# TTTQ20_STM32-project__Schematic1_4__1_P1.net
KiCad netlist of a schematic drawn in Altium Designer
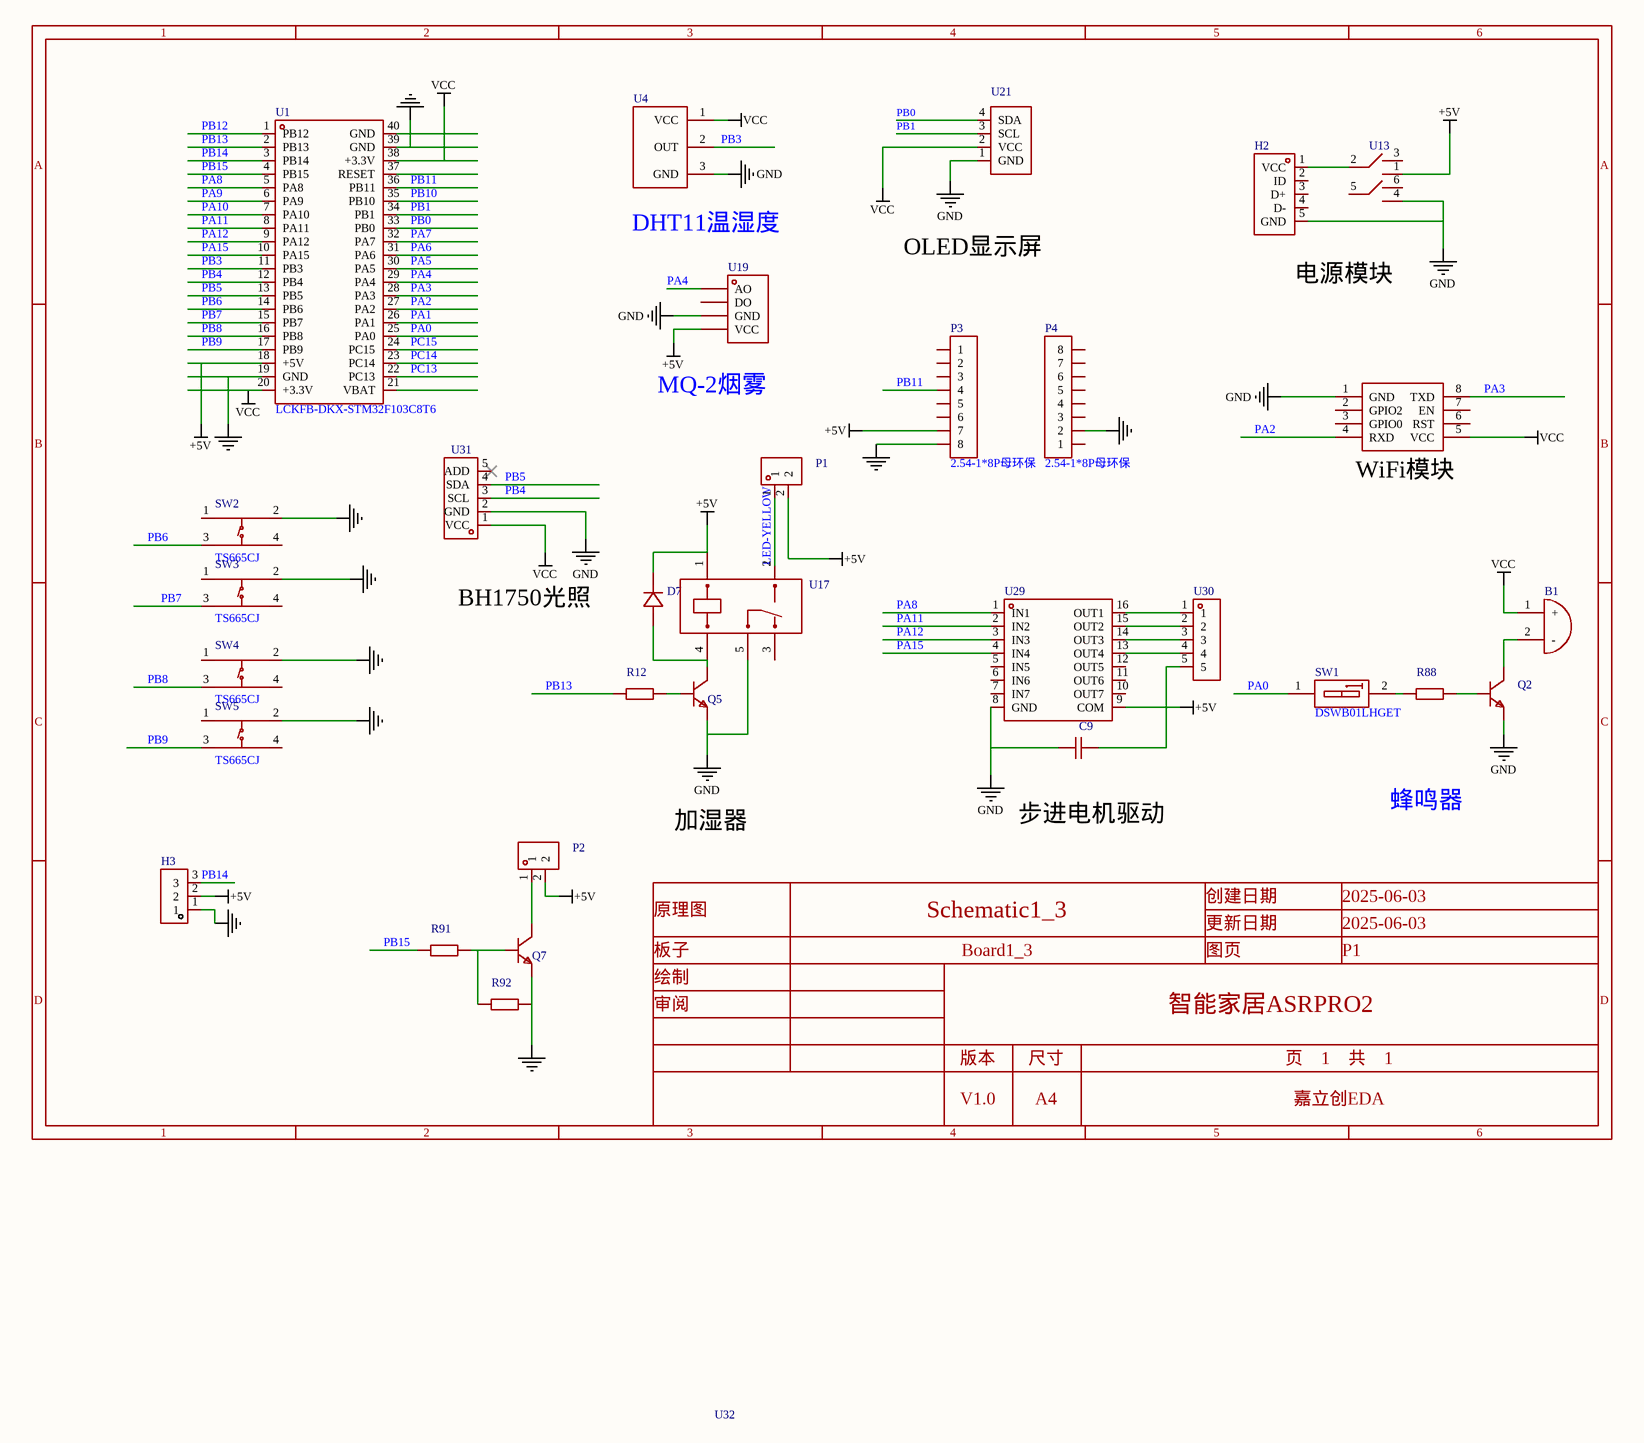
[diagram p0: TTTQ20_STM32-project__Schematic1_4__1_P1.schdoc]

(export (version "E")
  (design (tool "Eeschema 10.0.6"))
  (components
    (comp (ref "B1")
      (value "蜂鸣器FMQ")
      (footprint "footprint_3c01")
      (libsource (lib "altium-import") (part "root_0_蜂鸣器FMQ_"))
    )
    (comp (ref "C9")
      (value "瓷片电容47PF  3KV")
      (footprint "CAP-TH_L5.0-W4.0-P5.00-D1.0")
      (libsource (lib "altium-import") (part "root_0_瓷片电容47PF  3KV_"))
    )
    (comp (ref "D7")
      (value "D_1N4007A")
      (footprint "DO_1N4007")
      (libsource (lib "altium-import") (part "root_1_D_1N4007A_"))
    )
    (comp (ref "H2")
      (value "mini USB")
      (footprint "MINI-USB-POWER")
      (libsource (lib "altium-import") (part "root_0_mini USB_"))
    )
    (comp (ref "H3")
      (value "~")
      (footprint "HDR-TH_3P-P2.54-V-F")
      (libsource (lib "altium-import") (part "root_2_HDR-F_2.54_1x3P_"))
    )
    (comp (ref "P1")
      (value "XH2.54直插座-2P")
      (footprint "CONN-TH_XH2.54-2P")
      (libsource (lib "altium-import") (part "root_1_XH2.54直插座-2P_"))
    )
    (comp (ref "P2")
      (value "XH2.54直插座-2P")
      (footprint "CONN-TH_XH2.54-2P")
      (libsource (lib "altium-import") (part "root_1_XH2.54直插座-2P_"))
    )
    (comp (ref "P3")
      (value "2.54-1*8P母环保")
      (footprint "HDR-TH_8P-P2.54-V-F-1")
      (fields (field (name "MANUFACTURER") "BOOMELE(博穆精密)"))
      (libsource (lib "altium-import") (part "root_0_2.54-1*8P母环保_"))
    )
    (comp (ref "P4")
      (value "2.54-1*8P母环保")
      (footprint "HDR-TH_8P-P2.54-V-F-1")
      (fields (field (name "MANUFACTURER") "BOOMELE(博穆精密)"))
      (libsource (lib "altium-import") (part "root_2_2.54-1*8P母环保_"))
    )
    (comp (ref "Q2")
      (value "S8050_TO_NPN")
      (footprint "S8050_TO_92")
      (libsource (lib "altium-import") (part "root_0_S8050_TO_NPN_"))
    )
    (comp (ref "Q5")
      (value "S8050_TO_NPN")
      (footprint "S8050_TO_92")
      (libsource (lib "altium-import") (part "root_0_S8050_TO_NPN_"))
    )
    (comp (ref "Q7")
      (value "S8050_TO_NPN")
      (footprint "S8050_TO_92")
      (libsource (lib "altium-import") (part "root_0_S8050_TO_NPN_"))
    )
    (comp (ref "R12")
      (value "1K")
      (footprint "Res_1/4W")
      (libsource (lib "altium-import") (part "root_2_1K_"))
    )
    (comp (ref "R88")
      (value "10kΩ")
      (footprint "Res_1/4W")
      (libsource (lib "altium-import") (part "root_0_10kΩ_"))
    )
    (comp (ref "R91")
      (value "10kΩ")
      (footprint "Res_1/4W")
      (libsource (lib "altium-import") (part "root_0_10kΩ_"))
    )
    (comp (ref "R92")
      (value "10kΩ")
      (footprint "Res_1/4W")
      (libsource (lib "altium-import") (part "root_0_10kΩ_"))
    )
    (comp (ref "SW1")
      (value "DSWB01LHGET")
      (footprint "SW-TH_DSWB01LHGET")
      (fields (field (name "MANUFACTURER") "YE"))
      (libsource (lib "altium-import") (part "root_0_DSWB01LHGET_"))
    )
    (comp (ref "SW2")
      (value "TS665CJ")
      (footprint "SW-TH_4P-L6.0-W6.0-P4.50-LS6.5")
      (fields (field (name "MANUFACTURER") "SHOU HAN(首韩)"))
      (libsource (lib "altium-import") (part "root_0_TS665CJ_"))
    )
    (comp (ref "SW3")
      (value "TS665CJ")
      (footprint "SW-TH_4P-L6.0-W6.0-P4.50-LS6.5")
      (fields (field (name "MANUFACTURER") "SHOU HAN(首韩)"))
      (libsource (lib "altium-import") (part "root_0_TS665CJ_"))
    )
    (comp (ref "SW4")
      (value "TS665CJ")
      (footprint "SW-TH_4P-L6.0-W6.0-P4.50-LS6.5")
      (fields (field (name "MANUFACTURER") "SHOU HAN(首韩)"))
      (libsource (lib "altium-import") (part "root_0_TS665CJ_"))
    )
    (comp (ref "SW5")
      (value "TS665CJ")
      (footprint "SW-TH_4P-L6.0-W6.0-P4.50-LS6.5")
      (fields (field (name "MANUFACTURER") "SHOU HAN(首韩)"))
      (libsource (lib "altium-import") (part "root_0_TS665CJ_"))
    )
    (comp (ref "U1")
      (value "LCKFB-DKX-STM32F103C8T6")
      (footprint "CONN-TH_L53.3-W22.9_STM32F103C8T6-CARD")
      (fields (field (name "MANUFACTURER") "立创开发板"))
      (libsource (lib "altium-import") (part "root_0_LCKFB-DKX-STM32F103C8T6_"))
    )
    (comp (ref "U4")
      (value "DHT11温湿度传感器")
      (footprint "DHT11")
      (libsource (lib "altium-import") (part "root_2_DHT11温湿度传感器_"))
    )
    (comp (ref "U13")
      (value "按键开关7*7")
      (footprint "footprint_7245")
      (libsource (lib "altium-import") (part "root_0_按键开关7*7_"))
    )
    (comp (ref "U17")
      (value "继电器5V")
      (footprint "footprint_0775")
      (libsource (lib "altium-import") (part "root_3_继电器5V_"))
    )
    (comp (ref "U19")
      (value "MQ系列4针传感器")
      (footprint "footprint_df71")
      (libsource (lib "altium-import") (part "root_0_MQ系列4针传感器_"))
    )
    (comp (ref "U21")
      (value "OLED四针0.96寸")
      (footprint "footprint_0ab5")
      (libsource (lib "altium-import") (part "root_0_OLED四针0.96寸_"))
    )
    (comp (ref "U29")
      (value "ULN2003A")
      (footprint "DIP-16_L20.0-W6.4-P2.54-LS7.6-BL")
      (fields (field (name "MANUFACTURER") "ST(意法半导体)"))
      (libsource (lib "altium-import") (part "root_0_ULN2003A_"))
    )
    (comp (ref "U30")
      (value "步进电机")
      (footprint "conn-th_5p-p2.54_xh2.54_5p_dip")
      (libsource (lib "altium-import") (part "root_0_步进电机_"))
    )
    (comp (ref "U31")
      (value "GY302光照传感器")
      (footprint "footprint_6163")
      (libsource (lib "altium-import") (part "root_0_GY302光照传感器_"))
    )
    (comp (ref "U32")
      (value "ESP8266-01S模块")
      (footprint "footprint_fe65")
      (libsource (lib "altium-import") (part "root_0_ESP8266-01S模块_"))
    )
  )
  (nets
    (net (code "1") (name "+5V") (class "Default")
      (node (ref "C9") (pin "2") (pinfunction "2_2") (pintype "passive"))
      (node (ref "D7") (pin "1") (pinfunction "K_1") (pintype "passive"))
      (node (ref "H3") (pin "2") (pinfunction "2_2") (pintype "passive"))
      (node (ref "P1") (pin "2") (pinfunction "2_2") (pintype "passive"))
      (node (ref "P2") (pin "2") (pinfunction "2_2") (pintype "passive"))
      (node (ref "P3") (pin "7") (pinfunction "7_7") (pintype "passive"))
      (node (ref "U1") (pin "18") (pinfunction "+5V_18") (pintype "passive"))
      (node (ref "U13") (pin "1") (pinfunction "1_1") (pintype "passive"))
      (node (ref "U17") (pin "1") (pinfunction "1_1") (pintype "passive"))
      (node (ref "U19") (pin "4") (pinfunction "VCC_4") (pintype "passive"))
      (node (ref "U29") (pin "9") (pinfunction "COM_9") (pintype "passive"))
      (node (ref "U30") (pin "5") (pinfunction "5_5") (pintype "passive"))
    )
    (net (code "2") (name "/LED-YELLOW") (class "Default")
      (node (ref "P1") (pin "1") (pinfunction "1_1") (pintype "passive"))
      (node (ref "U17") (pin "2") (pinfunction "2_2") (pintype "passive"))
    )
    (net (code "3") (name "/PA0") (class "Default")
      (node (ref "SW1") (pin "1") (pinfunction "A1_1") (pintype "passive"))
      (node (ref "U1") (pin "25") (pinfunction "PA0_25") (pintype "passive"))
    )
    (net (code "4") (name "/PA1") (class "Default")
      (node (ref "U1") (pin "26") (pinfunction "PA1_26") (pintype "passive"))
    )
    (net (code "5") (name "/PA2") (class "Default")
      (node (ref "U1") (pin "27") (pinfunction "PA2_27") (pintype "passive"))
      (node (ref "U32") (pin "4") (pinfunction "RXD_4") (pintype "passive"))
    )
    (net (code "6") (name "/PA3") (class "Default")
      (node (ref "U1") (pin "28") (pinfunction "PA3_28") (pintype "passive"))
      (node (ref "U32") (pin "8") (pinfunction "TXD_8") (pintype "passive"))
    )
    (net (code "7") (name "/PA4") (class "Default")
      (node (ref "U1") (pin "29") (pinfunction "PA4_29") (pintype "passive"))
      (node (ref "U19") (pin "1") (pinfunction "AO_1") (pintype "passive"))
    )
    (net (code "8") (name "/PA5") (class "Default")
      (node (ref "U1") (pin "30") (pinfunction "PA5_30") (pintype "passive"))
    )
    (net (code "9") (name "/PA6") (class "Default")
      (node (ref "U1") (pin "31") (pinfunction "PA6_31") (pintype "passive"))
    )
    (net (code "10") (name "/PA7") (class "Default")
      (node (ref "U1") (pin "32") (pinfunction "PA7_32") (pintype "passive"))
    )
    (net (code "11") (name "/PA8") (class "Default")
      (node (ref "U1") (pin "5") (pinfunction "PA8_5") (pintype "passive"))
      (node (ref "U29") (pin "1") (pinfunction "IN1_1") (pintype "passive"))
    )
    (net (code "12") (name "/PA9") (class "Default")
      (node (ref "U1") (pin "6") (pinfunction "PA9_6") (pintype "passive"))
    )
    (net (code "13") (name "/PA10") (class "Default")
      (node (ref "U1") (pin "7") (pinfunction "PA10_7") (pintype "passive"))
    )
    (net (code "14") (name "/PA11") (class "Default")
      (node (ref "U1") (pin "8") (pinfunction "PA11_8") (pintype "passive"))
      (node (ref "U29") (pin "2") (pinfunction "IN2_2") (pintype "passive"))
    )
    (net (code "15") (name "/PA12") (class "Default")
      (node (ref "U1") (pin "9") (pinfunction "PA12_9") (pintype "passive"))
      (node (ref "U29") (pin "3") (pinfunction "IN3_3") (pintype "passive"))
    )
    (net (code "16") (name "/PA15") (class "Default")
      (node (ref "U1") (pin "10") (pinfunction "PA15_10") (pintype "passive"))
      (node (ref "U29") (pin "4") (pinfunction "IN4_4") (pintype "passive"))
    )
    (net (code "17") (name "/PB0") (class "Default")
      (node (ref "U1") (pin "33") (pinfunction "PB0_33") (pintype "passive"))
      (node (ref "U21") (pin "4") (pinfunction "SDA_4") (pintype "passive"))
    )
    (net (code "18") (name "/PB1") (class "Default")
      (node (ref "U1") (pin "34") (pinfunction "PB1_34") (pintype "passive"))
      (node (ref "U21") (pin "3") (pinfunction "SCL_3") (pintype "passive"))
    )
    (net (code "19") (name "/PB3") (class "Default")
      (node (ref "U1") (pin "11") (pinfunction "PB3_11") (pintype "passive"))
      (node (ref "U4") (pin "2") (pinfunction "OUT_2") (pintype "passive"))
    )
    (net (code "20") (name "/PB4") (class "Default")
      (node (ref "U1") (pin "12") (pinfunction "PB4_12") (pintype "passive"))
      (node (ref "U31") (pin "3") (pinfunction "SCL_3") (pintype "passive"))
    )
    (net (code "21") (name "/PB5") (class "Default")
      (node (ref "U1") (pin "13") (pinfunction "PB5_13") (pintype "passive"))
      (node (ref "U31") (pin "4") (pinfunction "SDA_4") (pintype "passive"))
    )
    (net (code "22") (name "/PB6") (class "Default")
      (node (ref "SW2") (pin "3") (pinfunction "C_3") (pintype "passive"))
      (node (ref "U1") (pin "14") (pinfunction "PB6_14") (pintype "passive"))
    )
    (net (code "23") (name "/PB7") (class "Default")
      (node (ref "SW3") (pin "3") (pinfunction "C_3") (pintype "passive"))
      (node (ref "U1") (pin "15") (pinfunction "PB7_15") (pintype "passive"))
    )
    (net (code "24") (name "/PB8") (class "Default")
      (node (ref "SW4") (pin "3") (pinfunction "C_3") (pintype "passive"))
      (node (ref "U1") (pin "16") (pinfunction "PB8_16") (pintype "passive"))
    )
    (net (code "25") (name "/PB9") (class "Default")
      (node (ref "SW5") (pin "3") (pinfunction "C_3") (pintype "passive"))
      (node (ref "U1") (pin "17") (pinfunction "PB9_17") (pintype "passive"))
    )
    (net (code "26") (name "/PB10") (class "Default")
      (node (ref "U1") (pin "35") (pinfunction "PB10_35") (pintype "passive"))
    )
    (net (code "27") (name "/PB11") (class "Default")
      (node (ref "P3") (pin "4") (pinfunction "4_4") (pintype "passive"))
      (node (ref "U1") (pin "36") (pinfunction "PB11_36") (pintype "passive"))
    )
    (net (code "28") (name "/PB12") (class "Default")
      (node (ref "U1") (pin "1") (pinfunction "PB12_1") (pintype "passive"))
    )
    (net (code "29") (name "/PB13") (class "Default")
      (node (ref "R12") (pin "2") (pinfunction "2_2") (pintype "passive"))
      (node (ref "U1") (pin "2") (pinfunction "PB13_2") (pintype "passive"))
    )
    (net (code "30") (name "/PB14") (class "Default")
      (node (ref "H3") (pin "3") (pinfunction "3_3") (pintype "passive"))
      (node (ref "U1") (pin "3") (pinfunction "PB14_3") (pintype "passive"))
    )
    (net (code "31") (name "/PB15") (class "Default")
      (node (ref "R91") (pin "1") (pinfunction "1_1") (pintype "passive"))
      (node (ref "U1") (pin "4") (pinfunction "PB15_4") (pintype "passive"))
    )
    (net (code "32") (name "/PC13") (class "Default")
      (node (ref "U1") (pin "22") (pinfunction "PC13_22") (pintype "passive"))
    )
    (net (code "33") (name "/PC14") (class "Default")
      (node (ref "U1") (pin "23") (pinfunction "PC14_23") (pintype "passive"))
    )
    (net (code "34") (name "/PC15") (class "Default")
      (node (ref "U1") (pin "24") (pinfunction "PC15_24") (pintype "passive"))
    )
    (net (code "35") (name "GND") (class "Default")
      (node (ref "C9") (pin "1") (pinfunction "1_1") (pintype "passive"))
      (node (ref "H2") (pin "5") (pinfunction "GND_5") (pintype "passive"))
      (node (ref "H3") (pin "1") (pinfunction "1_1") (pintype "passive"))
      (node (ref "P3") (pin "8") (pinfunction "8_8") (pintype "passive"))
      (node (ref "P4") (pin "2") (pinfunction "2_2") (pintype "passive"))
      (node (ref "Q2") (pin "1") (pinfunction "E_1") (pintype "passive"))
      (node (ref "Q5") (pin "1") (pinfunction "E_1") (pintype "passive"))
      (node (ref "Q7") (pin "1") (pinfunction "E_1") (pintype "passive"))
      (node (ref "R92") (pin "2") (pinfunction "2_2") (pintype "passive"))
      (node (ref "SW2") (pin "2") (pinfunction "B_2") (pintype "passive"))
      (node (ref "SW3") (pin "2") (pinfunction "B_2") (pintype "passive"))
      (node (ref "SW4") (pin "2") (pinfunction "B_2") (pintype "passive"))
      (node (ref "SW5") (pin "2") (pinfunction "B_2") (pintype "passive"))
      (node (ref "U1") (pin "19") (pinfunction "GND_19") (pintype "passive"))
      (node (ref "U1") (pin "39") (pinfunction "GND_39") (pintype "passive"))
      (node (ref "U1") (pin "40") (pinfunction "GND_40") (pintype "passive"))
      (node (ref "U13") (pin "4") (pinfunction "4_4") (pintype "passive"))
      (node (ref "U17") (pin "5") (pinfunction "5_5") (pintype "passive"))
      (node (ref "U19") (pin "3") (pinfunction "GND_3") (pintype "passive"))
      (node (ref "U21") (pin "1") (pinfunction "GND_1") (pintype "passive"))
      (node (ref "U29") (pin "8") (pinfunction "GND_8") (pintype "passive"))
      (node (ref "U31") (pin "2") (pinfunction "GND_2") (pintype "passive"))
      (node (ref "U32") (pin "1") (pinfunction "GND_1") (pintype "passive"))
      (node (ref "U4") (pin "3") (pinfunction "GND_3") (pintype "passive"))
    )
    (net (code "36") (name "Net-(B1--)") (class "Default")
      (node (ref "B1") (pin "2") (pinfunction "-_2") (pintype "passive"))
      (node (ref "Q2") (pin "3") (pinfunction "C_3") (pintype "passive"))
    )
    (net (code "37") (name "Net-(D7-A)") (class "Default")
      (node (ref "D7") (pin "2") (pinfunction "A_2") (pintype "passive"))
      (node (ref "Q5") (pin "3") (pinfunction "C_3") (pintype "passive"))
      (node (ref "U17") (pin "4") (pinfunction "4_4") (pintype "passive"))
    )
    (net (code "38") (name "Net-(H2-VCC)") (class "Default")
      (node (ref "H2") (pin "1") (pinfunction "VCC_1") (pintype "passive"))
      (node (ref "U13") (pin "2") (pinfunction "2_2") (pintype "passive"))
    )
    (net (code "39") (name "Net-(Q2-B)") (class "Default")
      (node (ref "Q2") (pin "2") (pinfunction "B_2") (pintype "passive"))
      (node (ref "R88") (pin "2") (pinfunction "2_2") (pintype "passive"))
    )
    (net (code "40") (name "Net-(Q5-B)") (class "Default")
      (node (ref "Q5") (pin "2") (pinfunction "B_2") (pintype "passive"))
      (node (ref "R12") (pin "1") (pinfunction "1_1") (pintype "passive"))
    )
    (net (code "41") (name "Net-(Q7-B)") (class "Default")
      (node (ref "Q7") (pin "2") (pinfunction "B_2") (pintype "passive"))
      (node (ref "R91") (pin "2") (pinfunction "2_2") (pintype "passive"))
      (node (ref "R92") (pin "1") (pinfunction "1_1") (pintype "passive"))
    )
    (net (code "42") (name "Net-(Q7-C)") (class "Default")
      (node (ref "P2") (pin "1") (pinfunction "1_1") (pintype "passive"))
      (node (ref "Q7") (pin "3") (pinfunction "C_3") (pintype "passive"))
    )
    (net (code "43") (name "Net-(R88-Pad1)") (class "Default")
      (node (ref "R88") (pin "1") (pinfunction "1_1") (pintype "passive"))
      (node (ref "SW1") (pin "2") (pinfunction "2_2") (pintype "passive"))
    )
    (net (code "44") (name "Net-(U29-OUT1)") (class "Default")
      (node (ref "U29") (pin "16") (pinfunction "OUT1_16") (pintype "passive"))
      (node (ref "U30") (pin "1") (pinfunction "1_1") (pintype "passive"))
    )
    (net (code "45") (name "Net-(U29-OUT2)") (class "Default")
      (node (ref "U29") (pin "15") (pinfunction "OUT2_15") (pintype "passive"))
      (node (ref "U30") (pin "2") (pinfunction "2_2") (pintype "passive"))
    )
    (net (code "46") (name "Net-(U29-OUT3)") (class "Default")
      (node (ref "U29") (pin "14") (pinfunction "OUT3_14") (pintype "passive"))
      (node (ref "U30") (pin "3") (pinfunction "3_3") (pintype "passive"))
    )
    (net (code "47") (name "Net-(U29-OUT4)") (class "Default")
      (node (ref "U29") (pin "13") (pinfunction "OUT4_13") (pintype "passive"))
      (node (ref "U30") (pin "4") (pinfunction "4_4") (pintype "passive"))
    )
    (net (code "48") (name "VCC") (class "Default")
      (node (ref "B1") (pin "1") (pinfunction "+_1") (pintype "passive"))
      (node (ref "U1") (pin "20") (pinfunction "+3.3V_20") (pintype "passive"))
      (node (ref "U1") (pin "38") (pinfunction "+3.3V_38") (pintype "passive"))
      (node (ref "U21") (pin "2") (pinfunction "VCC_2") (pintype "passive"))
      (node (ref "U31") (pin "1") (pinfunction "VCC_1") (pintype "passive"))
      (node (ref "U32") (pin "5") (pinfunction "VCC_5") (pintype "passive"))
      (node (ref "U4") (pin "1") (pinfunction "VCC_1") (pintype "passive"))
    )
    (net (code "49") (name "unconnected-(H2-D+-Pad3)") (class "Default")
      (node (ref "H2") (pin "3") (pinfunction "D+_3") (pintype "passive"))
    )
    (net (code "50") (name "unconnected-(H2-D--Pad4)") (class "Default")
      (node (ref "H2") (pin "4") (pinfunction "D-_4") (pintype "passive"))
    )
    (net (code "51") (name "unconnected-(H2-ID-Pad2)") (class "Default")
      (node (ref "H2") (pin "2") (pinfunction "ID_2") (pintype "passive"))
    )
    (net (code "52") (name "unconnected-(P3-Pad1)") (class "Default")
      (node (ref "P3") (pin "1") (pinfunction "1_1") (pintype "passive"))
    )
    (net (code "53") (name "unconnected-(P3-Pad2)") (class "Default")
      (node (ref "P3") (pin "2") (pinfunction "2_2") (pintype "passive"))
    )
    (net (code "54") (name "unconnected-(P3-Pad3)") (class "Default")
      (node (ref "P3") (pin "3") (pinfunction "3_3") (pintype "passive"))
    )
    (net (code "55") (name "unconnected-(P3-Pad5)") (class "Default")
      (node (ref "P3") (pin "5") (pinfunction "5_5") (pintype "passive"))
    )
    (net (code "56") (name "unconnected-(P3-Pad6)") (class "Default")
      (node (ref "P3") (pin "6") (pinfunction "6_6") (pintype "passive"))
    )
    (net (code "57") (name "unconnected-(P4-Pad1)") (class "Default")
      (node (ref "P4") (pin "1") (pinfunction "1_1") (pintype "passive"))
    )
    (net (code "58") (name "unconnected-(P4-Pad3)") (class "Default")
      (node (ref "P4") (pin "3") (pinfunction "3_3") (pintype "passive"))
    )
    (net (code "59") (name "unconnected-(P4-Pad4)") (class "Default")
      (node (ref "P4") (pin "4") (pinfunction "4_4") (pintype "passive"))
    )
    (net (code "60") (name "unconnected-(P4-Pad5)") (class "Default")
      (node (ref "P4") (pin "5") (pinfunction "5_5") (pintype "passive"))
    )
    (net (code "61") (name "unconnected-(P4-Pad6)") (class "Default")
      (node (ref "P4") (pin "6") (pinfunction "6_6") (pintype "passive"))
    )
    (net (code "62") (name "unconnected-(P4-Pad7)") (class "Default")
      (node (ref "P4") (pin "7") (pinfunction "7_7") (pintype "passive"))
    )
    (net (code "63") (name "unconnected-(P4-Pad8)") (class "Default")
      (node (ref "P4") (pin "8") (pinfunction "8_8") (pintype "passive"))
    )
    (net (code "64") (name "unconnected-(SW2-A-Pad1)") (class "Default")
      (node (ref "SW2") (pin "1") (pinfunction "A_1") (pintype "passive"))
    )
    (net (code "65") (name "unconnected-(SW2-D-Pad4)") (class "Default")
      (node (ref "SW2") (pin "4") (pinfunction "D_4") (pintype "passive"))
    )
    (net (code "66") (name "unconnected-(SW3-A-Pad1)") (class "Default")
      (node (ref "SW3") (pin "1") (pinfunction "A_1") (pintype "passive"))
    )
    (net (code "67") (name "unconnected-(SW3-D-Pad4)") (class "Default")
      (node (ref "SW3") (pin "4") (pinfunction "D_4") (pintype "passive"))
    )
    (net (code "68") (name "unconnected-(SW4-A-Pad1)") (class "Default")
      (node (ref "SW4") (pin "1") (pinfunction "A_1") (pintype "passive"))
    )
    (net (code "69") (name "unconnected-(SW4-D-Pad4)") (class "Default")
      (node (ref "SW4") (pin "4") (pinfunction "D_4") (pintype "passive"))
    )
    (net (code "70") (name "unconnected-(SW5-A-Pad1)") (class "Default")
      (node (ref "SW5") (pin "1") (pinfunction "A_1") (pintype "passive"))
    )
    (net (code "71") (name "unconnected-(SW5-D-Pad4)") (class "Default")
      (node (ref "SW5") (pin "4") (pinfunction "D_4") (pintype "passive"))
    )
    (net (code "72") (name "unconnected-(U1-RESET-Pad37)") (class "Default")
      (node (ref "U1") (pin "37") (pinfunction "RESET_37") (pintype "passive"))
    )
    (net (code "73") (name "unconnected-(U1-VBAT-Pad21)") (class "Default")
      (node (ref "U1") (pin "21") (pinfunction "VBAT_21") (pintype "passive"))
    )
    (net (code "74") (name "unconnected-(U13-Pad3)") (class "Default")
      (node (ref "U13") (pin "3") (pinfunction "3_3") (pintype "passive"))
    )
    (net (code "75") (name "unconnected-(U13-Pad5)") (class "Default")
      (node (ref "U13") (pin "5") (pinfunction "5_5") (pintype "passive"))
    )
    (net (code "76") (name "unconnected-(U13-Pad6)") (class "Default")
      (node (ref "U13") (pin "6") (pinfunction "6_6") (pintype "passive"))
    )
    (net (code "77") (name "unconnected-(U17-Pad3)") (class "Default")
      (node (ref "U17") (pin "3") (pinfunction "3_3") (pintype "passive"))
    )
    (net (code "78") (name "unconnected-(U19-DO-Pad2)") (class "Default")
      (node (ref "U19") (pin "2") (pinfunction "DO_2") (pintype "passive"))
    )
    (net (code "79") (name "unconnected-(U29-IN5-Pad5)") (class "Default")
      (node (ref "U29") (pin "5") (pinfunction "IN5_5") (pintype "passive"))
    )
    (net (code "80") (name "unconnected-(U29-IN6-Pad6)") (class "Default")
      (node (ref "U29") (pin "6") (pinfunction "IN6_6") (pintype "passive"))
    )
    (net (code "81") (name "unconnected-(U29-IN7-Pad7)") (class "Default")
      (node (ref "U29") (pin "7") (pinfunction "IN7_7") (pintype "passive"))
    )
    (net (code "82") (name "unconnected-(U29-OUT5-Pad12)") (class "Default")
      (node (ref "U29") (pin "12") (pinfunction "OUT5_12") (pintype "passive"))
    )
    (net (code "83") (name "unconnected-(U29-OUT6-Pad11)") (class "Default")
      (node (ref "U29") (pin "11") (pinfunction "OUT6_11") (pintype "passive"))
    )
    (net (code "84") (name "unconnected-(U29-OUT7-Pad10)") (class "Default")
      (node (ref "U29") (pin "10") (pinfunction "OUT7_10") (pintype "passive"))
    )
    (net (code "85") (name "unconnected-(U31-ADD-Pad5)") (class "Default")
      (node (ref "U31") (pin "5") (pinfunction "ADD_5") (pintype "passive+no_connect"))
    )
    (net (code "86") (name "unconnected-(U32-EN-Pad7)") (class "Default")
      (node (ref "U32") (pin "7") (pinfunction "EN_7") (pintype "passive"))
    )
    (net (code "87") (name "unconnected-(U32-GPIO0-Pad3)") (class "Default")
      (node (ref "U32") (pin "3") (pinfunction "GPIO0_3") (pintype "passive"))
    )
    (net (code "88") (name "unconnected-(U32-GPIO2-Pad2)") (class "Default")
      (node (ref "U32") (pin "2") (pinfunction "GPIO2_2") (pintype "passive"))
    )
    (net (code "89") (name "unconnected-(U32-RST-Pad6)") (class "Default")
      (node (ref "U32") (pin "6") (pinfunction "RST_6") (pintype "passive"))
    )
  )
)
